# esp32-driver.net
KiCad netlist of a schematic drawn in EAGLE
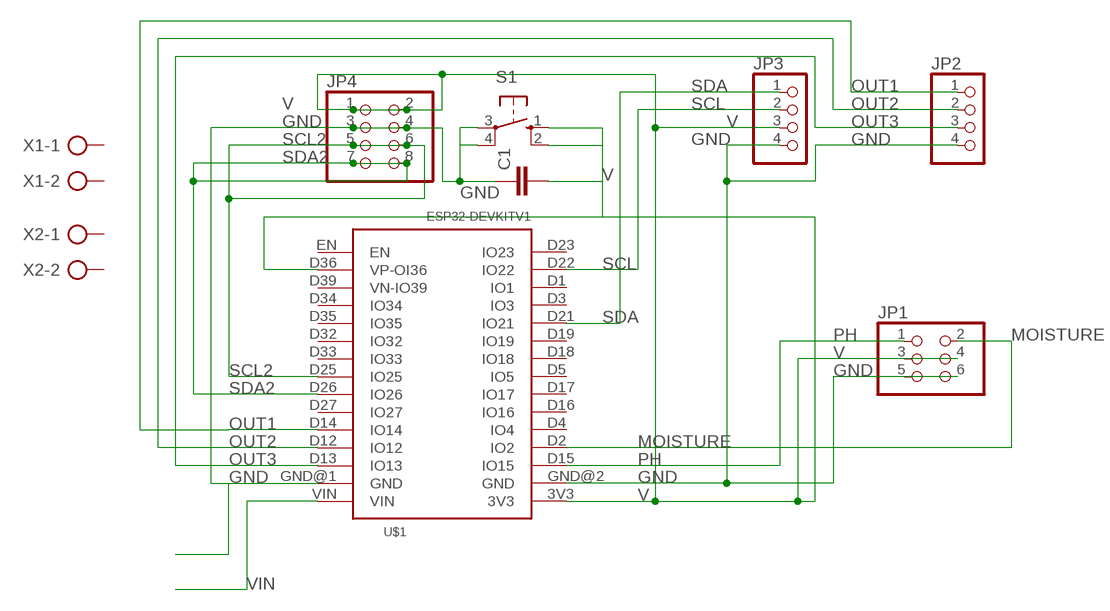
[diagram p0: schematic, sheet 1]

(export (version "E")
  (design (tool "Eeschema 10.0.6"))
  (components
    (comp (ref "C1")
      (value "C-EU050-030X075")
      (footprint "eagle-import:C050-030X075")
      (libsource (lib "eagle-import") (part "C-EU050-030X075"))
    )
    (comp (ref "JP1")
      (value "PINHD-2X3")
      (footprint "eagle-import:2X03")
      (libsource (lib "eagle-import") (part "PINHD-2X3"))
    )
    (comp (ref "JP2")
      (value "PINHD-1X4")
      (footprint "eagle-import:1X04")
      (libsource (lib "eagle-import") (part "PINHD-1X4"))
    )
    (comp (ref "JP3")
      (value "PINHD-1X4")
      (footprint "eagle-import:1X04")
      (libsource (lib "eagle-import") (part "PINHD-1X4"))
    )
    (comp (ref "JP4")
      (value "PINHD-2X4")
      (footprint "eagle-import:2X04")
      (libsource (lib "eagle-import") (part "PINHD-2X4"))
    )
    (comp (ref "S1")
      (value "10-XX")
      (footprint "eagle-import:B3F-10XX")
      (fields (field (name "MPN") "B3F-1000"))
      (libsource (lib "eagle-import") (part "10-XX"))
    )
    (comp (ref "U$1")
      (value "ESP32DEVKITV1")
      (footprint "eagle-import:ESP32-DEVKITV1")
      (libsource (lib "eagle-import") (part "ESP32DEVKITV1"))
    )
    (comp (ref "X1")
      (value "AK300/2")
      (footprint "eagle-import:AK300_2")
      (libsource (lib "eagle-import") (part "AK300/2"))
    )
    (comp (ref "X2")
      (value "AK300/2")
      (footprint "eagle-import:AK300_2")
      (libsource (lib "eagle-import") (part "AK300/2"))
    )
  )
  (nets
    (net (code "1") (name "/GND") (class "Default")
      (node (ref "C1") (pin "1") (pinfunction "1_1") (pintype "passive"))
      (node (ref "JP1") (pin "5") (pinfunction "5_5") (pintype "passive"))
      (node (ref "JP1") (pin "6") (pinfunction "6_6") (pintype "passive"))
      (node (ref "JP2") (pin "4") (pinfunction "4_4") (pintype "passive"))
      (node (ref "JP3") (pin "4") (pinfunction "4_4") (pintype "passive"))
      (node (ref "JP4") (pin "3") (pinfunction "3_3") (pintype "passive"))
      (node (ref "JP4") (pin "4") (pinfunction "4_4") (pintype "passive"))
      (node (ref "S1") (pin "3") (pinfunction "P_3") (pintype "passive"))
      (node (ref "S1") (pin "4") (pinfunction "P1_4") (pintype "passive"))
      (node (ref "U$1") (pin "GND@1") (pinfunction "GND_GND@1") (pintype "bidirectional"))
      (node (ref "U$1") (pin "GND@2") (pinfunction "GND_GND@2") (pintype "bidirectional"))
    )
    (net (code "2") (name "/MOISTURE") (class "Default")
      (node (ref "JP1") (pin "2") (pinfunction "2_2") (pintype "passive"))
      (node (ref "U$1") (pin "D2") (pinfunction "IO2_D2") (pintype "bidirectional"))
    )
    (net (code "3") (name "/OUT1") (class "Default")
      (node (ref "JP2") (pin "1") (pinfunction "1_1") (pintype "passive"))
      (node (ref "U$1") (pin "D14") (pinfunction "IO14_D14") (pintype "bidirectional"))
    )
    (net (code "4") (name "/OUT2") (class "Default")
      (node (ref "JP2") (pin "2") (pinfunction "2_2") (pintype "passive"))
      (node (ref "U$1") (pin "D12") (pinfunction "IO12_D12") (pintype "bidirectional"))
    )
    (net (code "5") (name "/OUT3") (class "Default")
      (node (ref "JP2") (pin "3") (pinfunction "3_3") (pintype "passive"))
      (node (ref "U$1") (pin "D13") (pinfunction "IO13_D13") (pintype "bidirectional"))
    )
    (net (code "6") (name "/PH") (class "Default")
      (node (ref "JP1") (pin "1") (pinfunction "1_1") (pintype "passive"))
      (node (ref "U$1") (pin "D15") (pinfunction "IO15_D15") (pintype "bidirectional"))
    )
    (net (code "7") (name "/SCL") (class "Default")
      (node (ref "JP3") (pin "2") (pinfunction "2_2") (pintype "passive"))
      (node (ref "U$1") (pin "D22") (pinfunction "IO22_D22") (pintype "bidirectional"))
    )
    (net (code "8") (name "/SCL2") (class "Default")
      (node (ref "JP4") (pin "5") (pinfunction "5_5") (pintype "passive"))
      (node (ref "JP4") (pin "6") (pinfunction "6_6") (pintype "passive"))
      (node (ref "U$1") (pin "D25") (pinfunction "IO25_D25") (pintype "bidirectional"))
    )
    (net (code "9") (name "/SDA") (class "Default")
      (node (ref "JP3") (pin "1") (pinfunction "1_1") (pintype "passive"))
      (node (ref "U$1") (pin "D21") (pinfunction "IO21_D21") (pintype "bidirectional"))
    )
    (net (code "10") (name "/SDA2") (class "Default")
      (node (ref "JP4") (pin "7") (pinfunction "7_7") (pintype "passive"))
      (node (ref "JP4") (pin "8") (pinfunction "8_8") (pintype "passive"))
      (node (ref "U$1") (pin "D26") (pinfunction "IO26_D26") (pintype "bidirectional"))
    )
    (net (code "11") (name "/V") (class "Default")
      (node (ref "C1") (pin "2") (pinfunction "2_2") (pintype "passive"))
      (node (ref "JP1") (pin "3") (pinfunction "3_3") (pintype "passive"))
      (node (ref "JP1") (pin "4") (pinfunction "4_4") (pintype "passive"))
      (node (ref "JP3") (pin "3") (pinfunction "3_3") (pintype "passive"))
      (node (ref "JP4") (pin "1") (pinfunction "1_1") (pintype "passive"))
      (node (ref "JP4") (pin "2") (pinfunction "2_2") (pintype "passive"))
      (node (ref "S1") (pin "1") (pinfunction "S_1") (pintype "passive"))
      (node (ref "S1") (pin "2") (pinfunction "S1_2") (pintype "passive"))
      (node (ref "U$1") (pin "3V3") (pinfunction "3V3_3V3") (pintype "bidirectional"))
      (node (ref "U$1") (pin "D36") (pinfunction "VP-OI36_D36") (pintype "bidirectional"))
    )
    (net (code "12") (name "/VIN") (class "Default")
      (node (ref "U$1") (pin "VIN") (pinfunction "VIN_VIN") (pintype "bidirectional"))
    )
    (net (code "13") (name "unconnected-(U$1-IO1-PadD1)") (class "Default")
      (node (ref "U$1") (pin "D1") (pinfunction "IO1_D1") (pintype "bidirectional"))
    )
    (net (code "14") (name "unconnected-(U$1-IO3-PadD3)") (class "Default")
      (node (ref "U$1") (pin "D3") (pinfunction "IO3_D3") (pintype "bidirectional"))
    )
    (net (code "15") (name "unconnected-(U$1-IO4-PadD4)") (class "Default")
      (node (ref "U$1") (pin "D4") (pinfunction "IO4_D4") (pintype "bidirectional"))
    )
    (net (code "16") (name "unconnected-(U$1-IO5-PadD5)") (class "Default")
      (node (ref "U$1") (pin "D5") (pinfunction "IO5_D5") (pintype "bidirectional"))
    )
    (net (code "17") (name "unconnected-(U$1-IO16-PadD16)") (class "Default")
      (node (ref "U$1") (pin "D16") (pinfunction "IO16_D16") (pintype "bidirectional"))
    )
    (net (code "18") (name "unconnected-(U$1-IO17-PadD17)") (class "Default")
      (node (ref "U$1") (pin "D17") (pinfunction "IO17_D17") (pintype "bidirectional"))
    )
    (net (code "19") (name "unconnected-(U$1-IO18-PadD18)") (class "Default")
      (node (ref "U$1") (pin "D18") (pinfunction "IO18_D18") (pintype "bidirectional"))
    )
    (net (code "20") (name "unconnected-(U$1-IO19-PadD19)") (class "Default")
      (node (ref "U$1") (pin "D19") (pinfunction "IO19_D19") (pintype "bidirectional"))
    )
    (net (code "21") (name "unconnected-(U$1-IO23-PadD23)") (class "Default")
      (node (ref "U$1") (pin "D23") (pinfunction "IO23_D23") (pintype "bidirectional"))
    )
    (net (code "22") (name "unconnected-(U$1-IO27-PadD27)") (class "Default")
      (node (ref "U$1") (pin "D27") (pinfunction "IO27_D27") (pintype "bidirectional"))
    )
    (net (code "23") (name "unconnected-(U$1-IO32-PadD32)") (class "Default")
      (node (ref "U$1") (pin "D32") (pinfunction "IO32_D32") (pintype "bidirectional"))
    )
    (net (code "24") (name "unconnected-(U$1-IO33-PadD33)") (class "Default")
      (node (ref "U$1") (pin "D33") (pinfunction "IO33_D33") (pintype "bidirectional"))
    )
    (net (code "25") (name "unconnected-(U$1-IO34-PadD34)") (class "Default")
      (node (ref "U$1") (pin "D34") (pinfunction "IO34_D34") (pintype "bidirectional"))
    )
    (net (code "26") (name "unconnected-(U$1-IO35-PadD35)") (class "Default")
      (node (ref "U$1") (pin "D35") (pinfunction "IO35_D35") (pintype "bidirectional"))
    )
    (net (code "27") (name "unconnected-(U$1-PadEN)") (class "Default")
      (node (ref "U$1") (pin "EN") (pinfunction "EN_EN") (pintype "bidirectional"))
    )
    (net (code "28") (name "unconnected-(U$1-VN-IO39-PadD39)") (class "Default")
      (node (ref "U$1") (pin "D39") (pinfunction "VN-IO39_D39") (pintype "bidirectional"))
    )
    (net (code "29") (name "unconnected-(X1A-KL-Pad1)") (class "Default")
      (node (ref "X1") (pin "1") (pinfunction "KL_1") (pintype "passive"))
    )
    (net (code "30") (name "unconnected-(X1B-KL-Pad2)") (class "Default")
      (node (ref "X1") (pin "2") (pinfunction "KL_2") (pintype "passive"))
    )
    (net (code "31") (name "unconnected-(X2A-KL-Pad1)") (class "Default")
      (node (ref "X2") (pin "1") (pinfunction "KL_1") (pintype "passive"))
    )
    (net (code "32") (name "unconnected-(X2B-KL-Pad2)") (class "Default")
      (node (ref "X2") (pin "2") (pinfunction "KL_2") (pintype "passive"))
    )
  )
)
